# CS4272-breakout-board.net
KiCad netlist of a schematic drawn in EAGLE
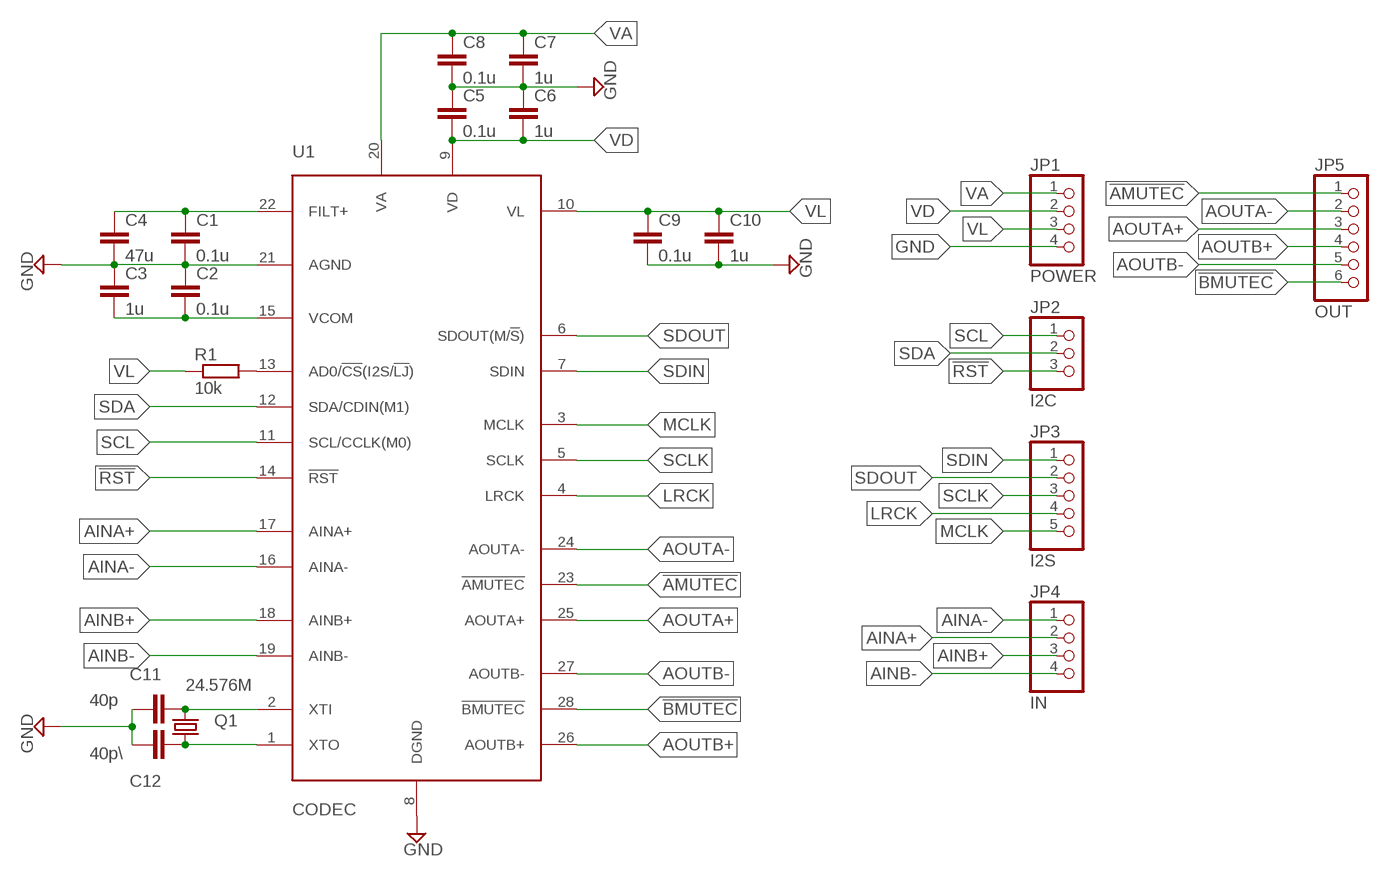
[diagram p0: schematic, sheet 1]

(export (version "E")
  (design (tool "Eeschema 10.0.6"))
  (components
    (comp (ref "C1")
      (value "0.1u")
      (footprint "eagle-import:C0603")
      (libsource (lib "eagle-import") (part "C-EUC0603"))
    )
    (comp (ref "C2")
      (value "0.1u")
      (footprint "eagle-import:C0603")
      (libsource (lib "eagle-import") (part "C-EUC0603"))
    )
    (comp (ref "C3")
      (value "1u")
      (footprint "eagle-import:C0603")
      (libsource (lib "eagle-import") (part "C-EUC0603"))
    )
    (comp (ref "C4")
      (value "47u")
      (footprint "eagle-import:C0603")
      (libsource (lib "eagle-import") (part "C-EUC0603"))
    )
    (comp (ref "C5")
      (value "0.1u")
      (footprint "eagle-import:C0603")
      (libsource (lib "eagle-import") (part "C-EUC0603"))
    )
    (comp (ref "C6")
      (value "1u")
      (footprint "eagle-import:C0603")
      (libsource (lib "eagle-import") (part "C-EUC0603"))
    )
    (comp (ref "C7")
      (value "1u")
      (footprint "eagle-import:C0603")
      (libsource (lib "eagle-import") (part "C-EUC0603"))
    )
    (comp (ref "C8")
      (value "0.1u")
      (footprint "eagle-import:C0603")
      (libsource (lib "eagle-import") (part "C-EUC0603"))
    )
    (comp (ref "C9")
      (value "0.1u")
      (footprint "eagle-import:C0603")
      (libsource (lib "eagle-import") (part "C-EUC0603"))
    )
    (comp (ref "C10")
      (value "1u")
      (footprint "eagle-import:C0603")
      (libsource (lib "eagle-import") (part "C-EUC0603"))
    )
    (comp (ref "C11")
      (value "40p")
      (footprint "eagle-import:C0603")
      (libsource (lib "eagle-import") (part "C-EUC0603"))
    )
    (comp (ref "C12")
      (value "40p\\")
      (footprint "eagle-import:C0603")
      (libsource (lib "eagle-import") (part "C-EUC0603"))
    )
    (comp (ref "JP1")
      (value "POWER")
      (footprint "eagle-import:1X04")
      (libsource (lib "eagle-import") (part "PINHD-1X4"))
    )
    (comp (ref "JP2")
      (value "I2C")
      (footprint "eagle-import:1X03")
      (libsource (lib "eagle-import") (part "PINHD-1X3"))
    )
    (comp (ref "JP3")
      (value "I2S")
      (footprint "eagle-import:1X05")
      (libsource (lib "eagle-import") (part "PINHD-1X5"))
    )
    (comp (ref "JP4")
      (value "IN")
      (footprint "eagle-import:1X04")
      (libsource (lib "eagle-import") (part "PINHD-1X4"))
    )
    (comp (ref "JP5")
      (value "OUT")
      (footprint "eagle-import:1X06")
      (libsource (lib "eagle-import") (part "PINHD-1X6"))
    )
    (comp (ref "Q1")
      (value "24.576M")
      (footprint "eagle-import:HC49U-V")
      (libsource (lib "eagle-import") (part "CRYSTALHC49U-V"))
    )
    (comp (ref "R1")
      (value "10k")
      (footprint "eagle-import:R0603")
      (libsource (lib "eagle-import") (part "R-EU_R0603"))
    )
    (comp (ref "U1")
      (value "CODEC")
      (footprint "eagle-import:TSSOP-28")
      (libsource (lib "eagle-import") (part "CS4272"))
    )
  )
  (nets
    (net (code "1") (name "/~{AMUTEC}") (class "Default")
      (node (ref "JP5") (pin "1") (pinfunction "1_1") (pintype "passive"))
      (node (ref "U1") (pin "23") (pinfunction "~{AMUTEC}_23") (pintype "output"))
    )
    (net (code "2") (name "/~{BMUTEC}") (class "Default")
      (node (ref "JP5") (pin "6") (pinfunction "6_6") (pintype "passive"))
      (node (ref "U1") (pin "28") (pinfunction "~{BMUTEC}_28") (pintype "output"))
    )
    (net (code "3") (name "/~{RST}") (class "Default")
      (node (ref "JP2") (pin "3") (pinfunction "3_3") (pintype "passive"))
      (node (ref "U1") (pin "14") (pinfunction "~{RST}_14") (pintype "input"))
    )
    (net (code "4") (name "AINA+") (class "Default")
      (node (ref "JP4") (pin "2") (pinfunction "2_2") (pintype "passive"))
      (node (ref "U1") (pin "17") (pinfunction "AINA+_17") (pintype "input"))
    )
    (net (code "5") (name "AINA-") (class "Default")
      (node (ref "JP4") (pin "1") (pinfunction "1_1") (pintype "passive"))
      (node (ref "U1") (pin "16") (pinfunction "AINA-_16") (pintype "input"))
    )
    (net (code "6") (name "AINB+") (class "Default")
      (node (ref "JP4") (pin "3") (pinfunction "3_3") (pintype "passive"))
      (node (ref "U1") (pin "18") (pinfunction "AINB+_18") (pintype "input"))
    )
    (net (code "7") (name "AINB-") (class "Default")
      (node (ref "JP4") (pin "4") (pinfunction "4_4") (pintype "passive"))
      (node (ref "U1") (pin "19") (pinfunction "AINB-_19") (pintype "input"))
    )
    (net (code "8") (name "AOUTA+") (class "Default")
      (node (ref "JP5") (pin "3") (pinfunction "3_3") (pintype "passive"))
      (node (ref "U1") (pin "25") (pinfunction "AOUTA+_25") (pintype "output"))
    )
    (net (code "9") (name "AOUTA-") (class "Default")
      (node (ref "JP5") (pin "2") (pinfunction "2_2") (pintype "passive"))
      (node (ref "U1") (pin "24") (pinfunction "AOUTA-_24") (pintype "output"))
    )
    (net (code "10") (name "AOUTB+") (class "Default")
      (node (ref "JP5") (pin "4") (pinfunction "4_4") (pintype "passive"))
      (node (ref "U1") (pin "26") (pinfunction "AOUTB+_26") (pintype "output"))
    )
    (net (code "11") (name "AOUTB-") (class "Default")
      (node (ref "JP5") (pin "5") (pinfunction "5_5") (pintype "passive"))
      (node (ref "U1") (pin "27") (pinfunction "AOUTB-_27") (pintype "output"))
    )
    (net (code "12") (name "GND") (class "Default")
      (node (ref "C1") (pin "2") (pinfunction "2_2") (pintype "passive"))
      (node (ref "C10") (pin "2") (pinfunction "2_2") (pintype "passive"))
      (node (ref "C11") (pin "1") (pinfunction "1_1") (pintype "passive"))
      (node (ref "C12") (pin "1") (pinfunction "1_1") (pintype "passive"))
      (node (ref "C2") (pin "1") (pinfunction "1_1") (pintype "passive"))
      (node (ref "C3") (pin "1") (pinfunction "1_1") (pintype "passive"))
      (node (ref "C4") (pin "2") (pinfunction "2_2") (pintype "passive"))
      (node (ref "C5") (pin "1") (pinfunction "1_1") (pintype "passive"))
      (node (ref "C6") (pin "1") (pinfunction "1_1") (pintype "passive"))
      (node (ref "C7") (pin "2") (pinfunction "2_2") (pintype "passive"))
      (node (ref "C8") (pin "2") (pinfunction "2_2") (pintype "passive"))
      (node (ref "C9") (pin "2") (pinfunction "2_2") (pintype "passive"))
      (node (ref "JP1") (pin "4") (pinfunction "4_4") (pintype "passive"))
      (node (ref "U1") (pin "21") (pinfunction "AGND_21") (pintype "bidirectional"))
      (node (ref "U1") (pin "8") (pinfunction "DGND_8") (pintype "input"))
    )
    (net (code "13") (name "LRCK") (class "Default")
      (node (ref "JP3") (pin "4") (pinfunction "4_4") (pintype "passive"))
      (node (ref "U1") (pin "4") (pinfunction "LRCK_4") (pintype "bidirectional"))
    )
    (net (code "14") (name "MCLK") (class "Default")
      (node (ref "JP3") (pin "5") (pinfunction "5_5") (pintype "passive"))
      (node (ref "U1") (pin "3") (pinfunction "MCLK_3") (pintype "bidirectional"))
    )
    (net (code "15") (name "Net-(U1-AD0{slash}~{CS}(I2S{slash}~{LJ}))") (class "Default")
      (node (ref "R1") (pin "2") (pinfunction "2_2") (pintype "passive"))
      (node (ref "U1") (pin "13") (pinfunction "AD0/~{CS}(I2S/~{LJ})_13") (pintype "input"))
    )
    (net (code "16") (name "Net-(U1-FILT+)") (class "Default")
      (node (ref "C1") (pin "1") (pinfunction "1_1") (pintype "passive"))
      (node (ref "C4") (pin "1") (pinfunction "1_1") (pintype "passive"))
      (node (ref "U1") (pin "22") (pinfunction "FILT+_22") (pintype "output"))
    )
    (net (code "17") (name "Net-(U1-VCOM)") (class "Default")
      (node (ref "C2") (pin "2") (pinfunction "2_2") (pintype "passive"))
      (node (ref "C3") (pin "2") (pinfunction "2_2") (pintype "passive"))
      (node (ref "U1") (pin "15") (pinfunction "VCOM_15") (pintype "output"))
    )
    (net (code "18") (name "Net-(U1-XTI)") (class "Default")
      (node (ref "C11") (pin "2") (pinfunction "2_2") (pintype "passive"))
      (node (ref "Q1") (pin "2") (pinfunction "2_2") (pintype "passive"))
      (node (ref "U1") (pin "2") (pinfunction "XTI_2") (pintype "bidirectional"))
    )
    (net (code "19") (name "Net-(U1-XTO)") (class "Default")
      (node (ref "C12") (pin "2") (pinfunction "2_2") (pintype "passive"))
      (node (ref "Q1") (pin "1") (pinfunction "1_1") (pintype "passive"))
      (node (ref "U1") (pin "1") (pinfunction "XTO_1") (pintype "bidirectional"))
    )
    (net (code "20") (name "SCL") (class "Default")
      (node (ref "JP2") (pin "1") (pinfunction "1_1") (pintype "passive"))
      (node (ref "U1") (pin "11") (pinfunction "SCL/CCLK(M0)_11") (pintype "input"))
    )
    (net (code "21") (name "SCLK") (class "Default")
      (node (ref "JP3") (pin "3") (pinfunction "3_3") (pintype "passive"))
      (node (ref "U1") (pin "5") (pinfunction "SCLK_5") (pintype "bidirectional"))
    )
    (net (code "22") (name "SDA") (class "Default")
      (node (ref "JP2") (pin "2") (pinfunction "2_2") (pintype "passive"))
      (node (ref "U1") (pin "12") (pinfunction "SDA/CDIN(M1)_12") (pintype "bidirectional"))
    )
    (net (code "23") (name "SDIN") (class "Default")
      (node (ref "JP3") (pin "1") (pinfunction "1_1") (pintype "passive"))
      (node (ref "U1") (pin "7") (pinfunction "SDIN_7") (pintype "input"))
    )
    (net (code "24") (name "SDOUT") (class "Default")
      (node (ref "JP3") (pin "2") (pinfunction "2_2") (pintype "passive"))
      (node (ref "U1") (pin "6") (pinfunction "SDOUT(M/~{S})_6") (pintype "output"))
    )
    (net (code "25") (name "VA") (class "Default")
      (node (ref "C7") (pin "1") (pinfunction "1_1") (pintype "passive"))
      (node (ref "C8") (pin "1") (pinfunction "1_1") (pintype "passive"))
      (node (ref "JP1") (pin "1") (pinfunction "1_1") (pintype "passive"))
      (node (ref "U1") (pin "20") (pinfunction "VA_20") (pintype "input"))
    )
    (net (code "26") (name "VD") (class "Default")
      (node (ref "C5") (pin "2") (pinfunction "2_2") (pintype "passive"))
      (node (ref "C6") (pin "2") (pinfunction "2_2") (pintype "passive"))
      (node (ref "JP1") (pin "2") (pinfunction "2_2") (pintype "passive"))
      (node (ref "U1") (pin "9") (pinfunction "VD_9") (pintype "input"))
    )
    (net (code "27") (name "VL") (class "Default")
      (node (ref "C10") (pin "1") (pinfunction "1_1") (pintype "passive"))
      (node (ref "C9") (pin "1") (pinfunction "1_1") (pintype "passive"))
      (node (ref "JP1") (pin "3") (pinfunction "3_3") (pintype "passive"))
      (node (ref "R1") (pin "1") (pinfunction "1_1") (pintype "passive"))
      (node (ref "U1") (pin "10") (pinfunction "VL_10") (pintype "input"))
    )
  )
)
